# 08-MagnetSensor.net
KiCad netlist of a schematic drawn in Altium Designer
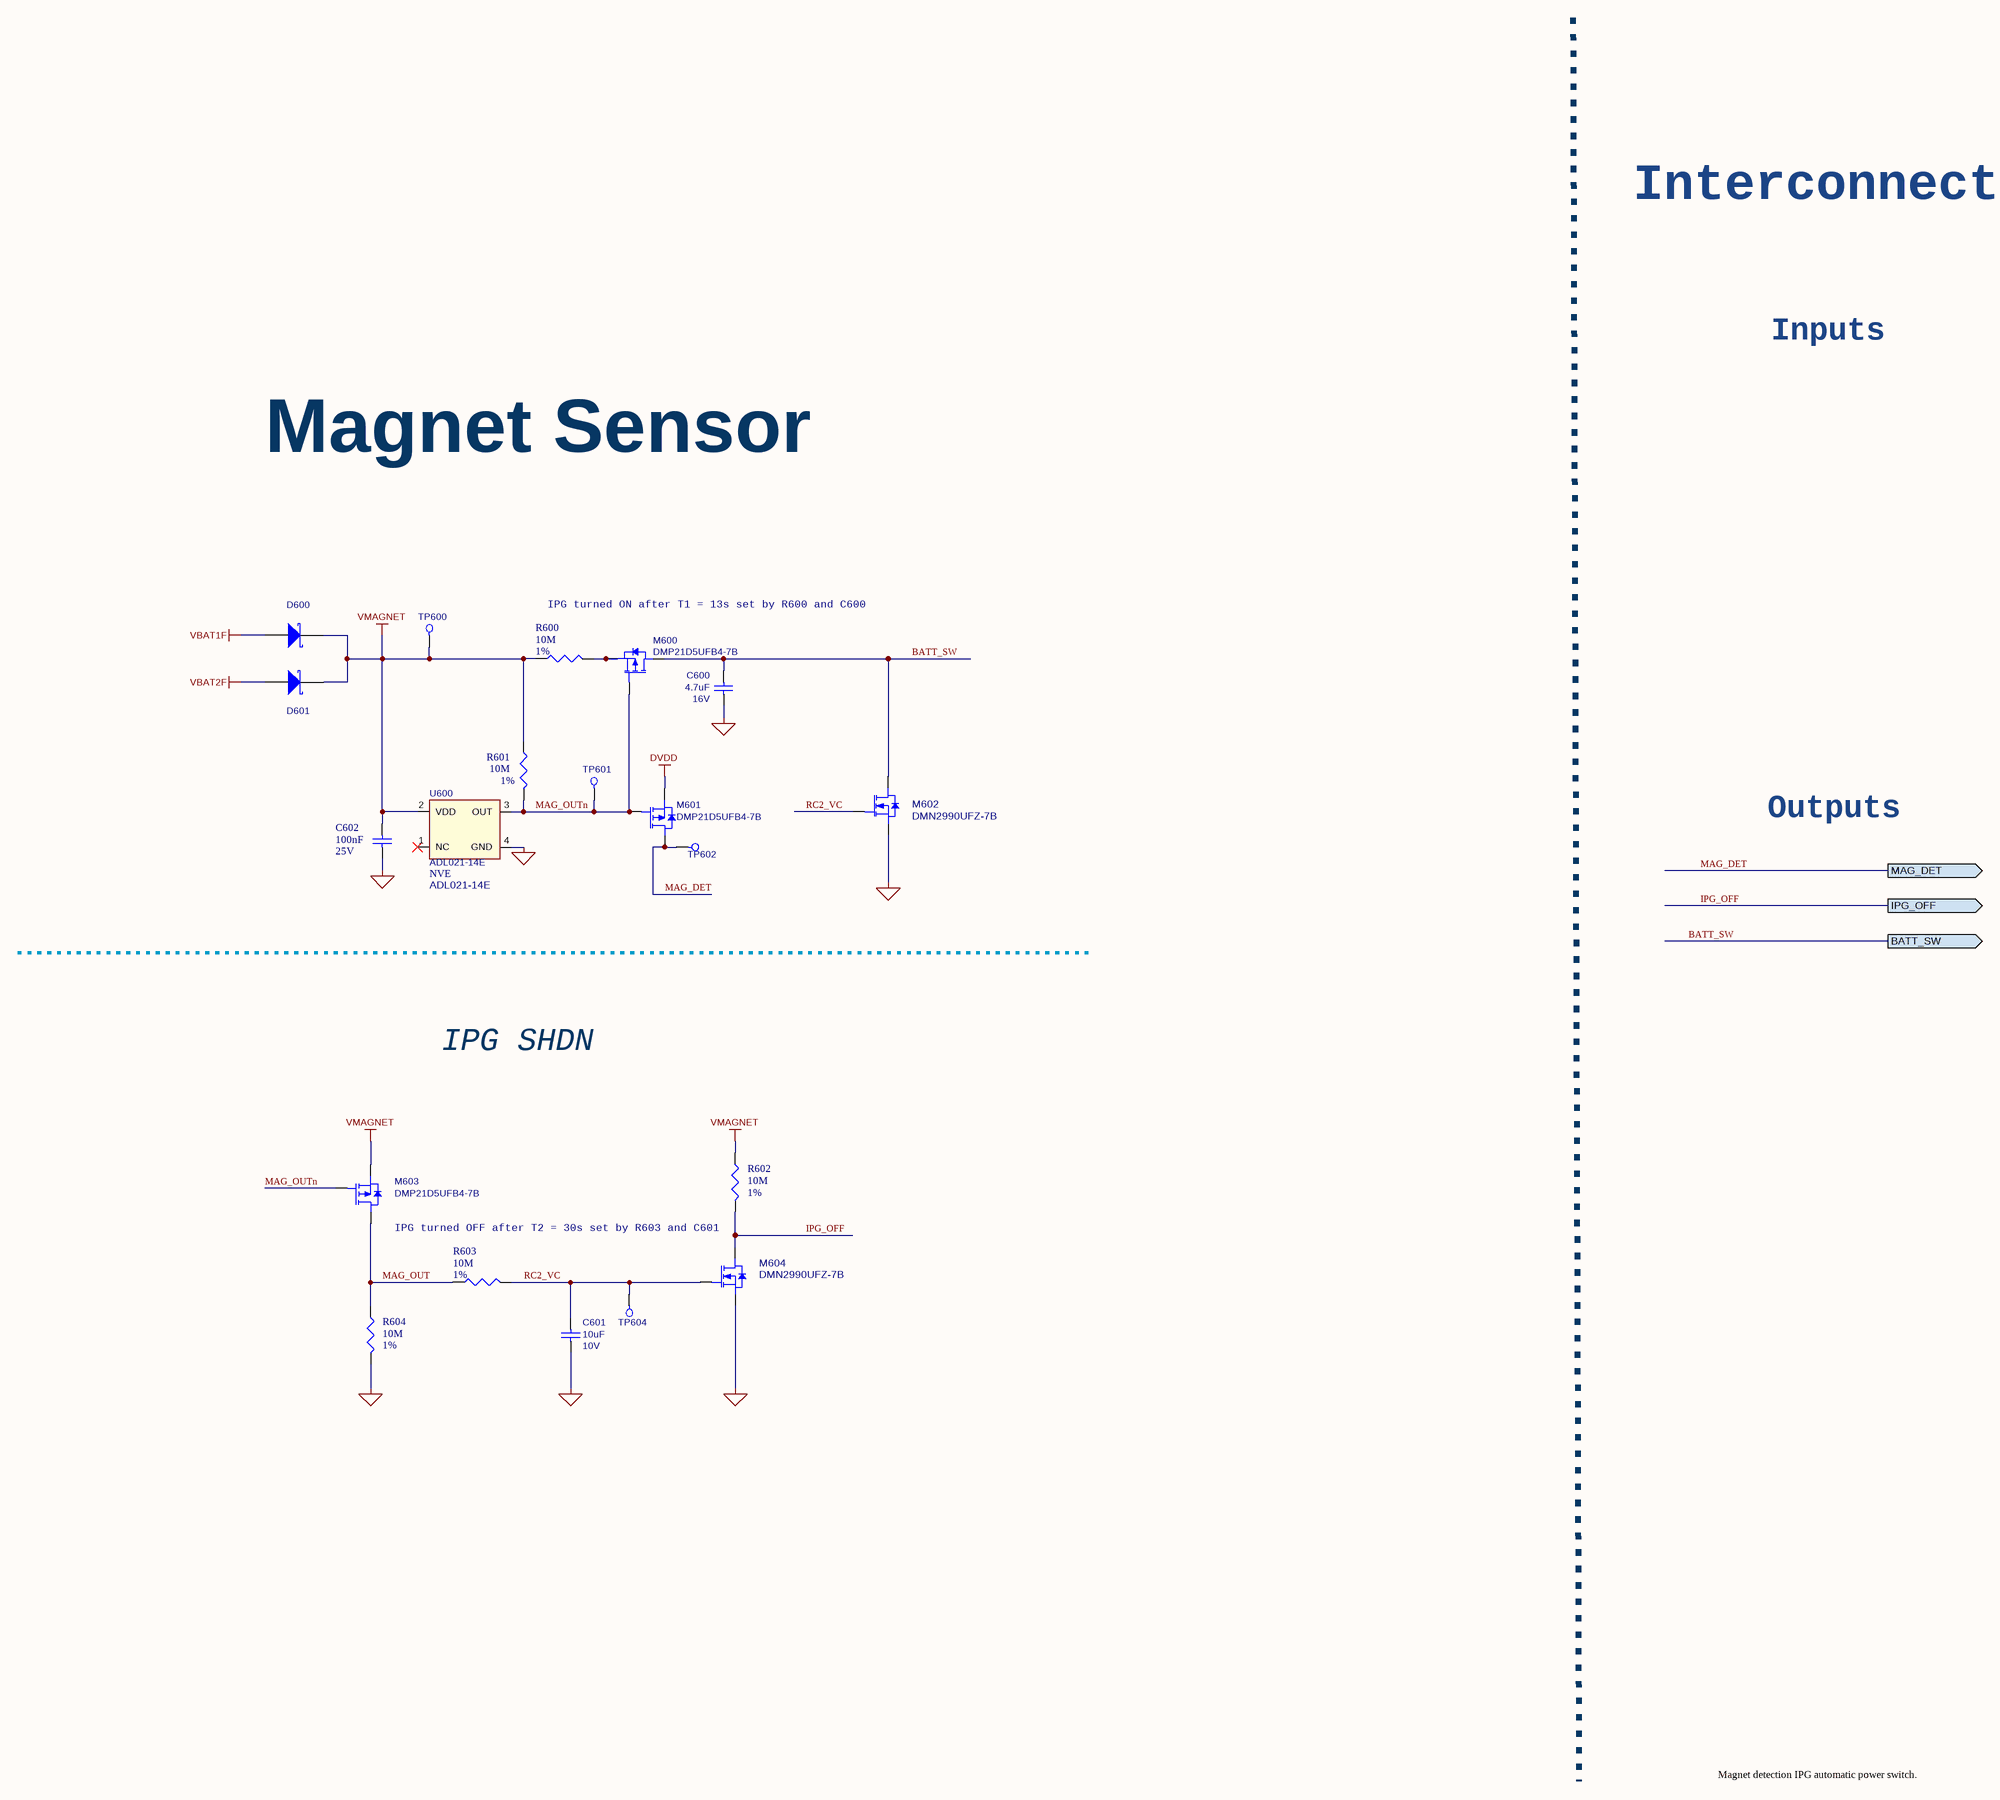
[diagram p0: 08-MagnetSensor.SchDoc]

(export (version "E")
  (design (tool "Eeschema 10.0.6"))
  (components
    (comp (ref "C600")
      (value "4.7uF")
      (footprint "CAP0603_REDUCED")
      (description "Capacitor, 4.7uF, X5R, 16V, 10%, 0603, Implant-grade")
      (fields
        (field (name "MANUFACTURER") "Murata")
        (field (name "RATING") "16V")
        (field (name "MANUFACTURER PART NUMBER") "GRM188R61C475KE11")
      )
      (libsource (lib "MP-LIBRARY") (part "GRM188R61C475KE11"))
    )
    (comp (ref "C601")
      (value "10uF")
      (footprint "CAP0402_REDUCED")
      (description "Capacitor, 10uf, X5R, 10V, 20%, 0402, Implant-grade")
      (fields
        (field (name "MANUFACTURER") "Murata")
        (field (name "RATING") "10V")
        (field (name "MANUFACTURER PART NUMBER") "ZRB15XR61A106ME01D")
      )
      (libsource (lib "MP-LIBRARY") (part "ZRB15XR61A106ME01D"))
    )
    (comp (ref "C602")
      (value "100nF")
      (footprint "C0201_C")
      (fields
        (field (name "MANUFACTURER") "Murata")
        (field (name "MANUFACTURER PART NUMBER") "GRM033R61E104KE14J")
        (field (name "RATED DC VOLTAGE (URDC)") "25V")
      )
      (libsource (lib "MP-LIBRARY") (part "GRM033R61E104KE14J"))
    )
    (comp (ref "D600")
      (value "NSR0130P2T5G")
      (footprint "ONSC_SOD-923_CASE514AB")
      (description "Schottky, 30V, 100mA, 385mV, 200mW, SOD-923")
      (fields (field (name "MANUFACTURER") "ON Semiconductor"))
      (libsource (lib "MP-LIBRARY") (part "NSR0130P2T5G"))
    )
    (comp (ref "D601")
      (value "NSR0130P2T5G")
      (footprint "ONSC_SOD-923_CASE514AB")
      (description "Schottky, 30V, 100mA, 385mV, 200mW, SOD-923")
      (fields (field (name "MANUFACTURER") "ON Semiconductor"))
      (libsource (lib "MP-LIBRARY") (part "NSR0130P2T5G"))
    )
    (comp (ref "M600")
      (value "DMP21D5UFB4-7B")
      (footprint "DIODESINC_X2-DFN1006-3_REDUCED")
      (description "MOSFET, P-chan, -20V, -400mA, X2-DFN1006-3")
      (fields (field (name "MANUFACTURER") "Diodes Inc"))
      (libsource (lib "MP-LIBRARY") (part "DMP21D5UFB4-7B"))
    )
    (comp (ref "M601")
      (value "DMP21D5UFB4-7B")
      (footprint "DIODESINC_X2-DFN1006-3_REDUCED")
      (description "MOSFET, P-chan, -20V, -400mA, X2-DFN1006-3")
      (fields (field (name "MANUFACTURER") "Diodes Inc"))
      (libsource (lib "MP-LIBRARY") (part "DMP21D5UFB4-7B"))
    )
    (comp (ref "M602")
      (value "DMN2990UFZ-7B")
      (footprint "DIODESINC_X2-DFN0606-3")
      (description "MOSFET, N-Chan, 20V, 170mA, DFN0606")
      (fields (field (name "MANUFACTURER") "Diodes Inc"))
      (libsource (lib "MP-LIBRARY") (part "DMN2990UFZ-7B"))
    )
    (comp (ref "M603")
      (value "DMP21D5UFB4-7B")
      (footprint "DIODESINC_X2-DFN1006-3_REDUCED")
      (description "MOSFET, P-chan, -20V, -400mA, X2-DFN1006-3")
      (fields (field (name "MANUFACTURER") "Diodes Inc"))
      (libsource (lib "MP-LIBRARY") (part "DMP21D5UFB4-7B"))
    )
    (comp (ref "M604")
      (value "DMN2990UFZ-7B")
      (footprint "DIODESINC_X2-DFN0606-3")
      (description "MOSFET, N-Chan, 20V, 170mA, DFN0606")
      (fields (field (name "MANUFACTURER") "Diodes Inc"))
      (libsource (lib "MP-LIBRARY") (part "DMN2990UFZ-7B"))
    )
    (comp (ref "R600")
      (value "10M")
      (footprint "R0201_C")
      (fields
        (field (name "MANUFACTURER") "Vishay Draloric")
        (field (name "MANUFACTURER PART NUMBER") "CRCW020110M0FNED")
        (field (name "TOLERANCE") "1%")
        (field (name "POWER") "50mW")
      )
      (libsource (lib "MP-LIBRARY") (part "CRCW020110M0FNED"))
    )
    (comp (ref "R601")
      (value "10M")
      (footprint "R0201_C")
      (fields
        (field (name "MANUFACTURER") "Vishay Draloric")
        (field (name "MANUFACTURER PART NUMBER") "CRCW020110M0FNED")
        (field (name "TOLERANCE") "1%")
        (field (name "POWER") "50mW")
      )
      (libsource (lib "MP-LIBRARY") (part "CRCW020110M0FNED"))
    )
    (comp (ref "R602")
      (value "10M")
      (footprint "R0201_C")
      (fields
        (field (name "MANUFACTURER") "Vishay Draloric")
        (field (name "MANUFACTURER PART NUMBER") "CRCW020110M0FNED")
        (field (name "TOLERANCE") "1%")
        (field (name "POWER") "50mW")
      )
      (libsource (lib "MP-LIBRARY") (part "CRCW020110M0FNED"))
    )
    (comp (ref "R603")
      (value "10M")
      (footprint "R0201_C")
      (fields
        (field (name "MANUFACTURER") "Vishay Draloric")
        (field (name "MANUFACTURER PART NUMBER") "CRCW020110M0FNED")
        (field (name "TOLERANCE") "1%")
        (field (name "POWER") "50mW")
      )
      (libsource (lib "MP-LIBRARY") (part "CRCW020110M0FNED"))
    )
    (comp (ref "R604")
      (value "10M")
      (footprint "R0201_C")
      (fields
        (field (name "MANUFACTURER") "Vishay Draloric")
        (field (name "MANUFACTURER PART NUMBER") "CRCW020110M0FNED")
        (field (name "TOLERANCE") "1%")
        (field (name "POWER") "50mW")
      )
      (libsource (lib "MP-LIBRARY") (part "CRCW020110M0FNED"))
    )
    (comp (ref "TP600")
      (value "Test Point")
      (footprint "testpad_0.9mm")
      (description "Test pad, 0.90mm circular pad")
      (libsource (lib "MP-LIBRARY") (part "Test Point"))
    )
    (comp (ref "TP601")
      (value "Test Point")
      (footprint "testpad_0.9mm")
      (description "Test pad, 0.90mm circular pad")
      (libsource (lib "MP-LIBRARY") (part "Test Point"))
    )
    (comp (ref "TP602")
      (value "Test Point")
      (footprint "testpad_0.9mm")
      (description "Test pad, 0.90mm circular pad")
      (libsource (lib "MP-LIBRARY") (part "Test Point"))
    )
    (comp (ref "TP604")
      (value "Test Point")
      (footprint "testpad_0.9mm")
      (description "Test pad, 0.90mm circular pad")
      (libsource (lib "MP-LIBRARY") (part "Test Point"))
    )
    (comp (ref "U600")
      (value "ADL021-14E")
      (footprint "NVE_ULLGA4")
      (description "Magnet Sensor, 15 Gauss, ULLGA4, Implant-grade")
      (fields (field (name "MANUFACTURER") "NVE") (field (name "ALTIUM_VALUE") "ADL021-14E"))
      (libsource (lib "MP-LIBRARY") (part "ADL021-14E"))
    )
  )
  (nets
    (net (code "1") (name "/BATT_SW") (class "Default")
      (node (ref "C600") (pin "1") (pinfunction "1_1") (pintype "passive"))
      (node (ref "M600") (pin "3") (pinfunction "D_3") (pintype "passive"))
      (node (ref "M602") (pin "3") (pinfunction "D_3") (pintype "passive"))
    )
    (net (code "2") (name "/IPG_OFF") (class "Default")
      (node (ref "M604") (pin "3") (pinfunction "D_3") (pintype "passive"))
      (node (ref "R602") (pin "2") (pinfunction "2_2") (pintype "passive"))
    )
    (net (code "3") (name "/MAG_DET") (class "Default")
      (node (ref "M601") (pin "3") (pinfunction "D_3") (pintype "passive"))
      (node (ref "TP602") (pin "1") (pinfunction "1_1") (pintype "passive"))
    )
    (net (code "4") (name "/MAG_OUT") (class "Default")
      (node (ref "M603") (pin "3") (pinfunction "D_3") (pintype "passive"))
      (node (ref "R603") (pin "1") (pinfunction "1_1") (pintype "passive"))
      (node (ref "R604") (pin "1") (pinfunction "1_1") (pintype "passive"))
    )
    (net (code "5") (name "/MAG_OUTn") (class "Default")
      (node (ref "M600") (pin "1") (pinfunction "G_1") (pintype "passive"))
      (node (ref "M601") (pin "1") (pinfunction "G_1") (pintype "passive"))
      (node (ref "M603") (pin "1") (pinfunction "G_1") (pintype "passive"))
      (node (ref "R601") (pin "2") (pinfunction "2_2") (pintype "passive"))
      (node (ref "TP601") (pin "1") (pinfunction "1_1") (pintype "passive"))
      (node (ref "U600") (pin "3") (pinfunction "OUT_3") (pintype "passive"))
    )
    (net (code "6") (name "/RC2_VC") (class "Default")
      (node (ref "C601") (pin "2") (pinfunction "2_2") (pintype "passive"))
      (node (ref "M602") (pin "1") (pinfunction "G_1") (pintype "passive"))
      (node (ref "M604") (pin "1") (pinfunction "G_1") (pintype "passive"))
      (node (ref "R603") (pin "2") (pinfunction "2_2") (pintype "passive"))
      (node (ref "TP604") (pin "1") (pinfunction "1_1") (pintype "passive"))
    )
    (net (code "7") (name "DVDD") (class "Default")
      (node (ref "M601") (pin "2") (pinfunction "S_2") (pintype "passive"))
    )
    (net (code "8") (name "GND") (class "Default")
      (node (ref "C600") (pin "2") (pinfunction "2_2") (pintype "passive"))
      (node (ref "C601") (pin "1") (pinfunction "1_1") (pintype "passive"))
      (node (ref "C602") (pin "1") (pinfunction "1_1") (pintype "passive"))
      (node (ref "M602") (pin "2") (pinfunction "S_2") (pintype "passive"))
      (node (ref "M604") (pin "2") (pinfunction "S_2") (pintype "passive"))
      (node (ref "R604") (pin "2") (pinfunction "2_2") (pintype "passive"))
      (node (ref "U600") (pin "4") (pinfunction "GND_4") (pintype "power_in"))
    )
    (net (code "9") (name "Net-(M600-S)") (class "Default")
      (node (ref "M600") (pin "2") (pinfunction "S_2") (pintype "passive"))
      (node (ref "R600") (pin "2") (pinfunction "2_2") (pintype "passive"))
    )
    (net (code "10") (name "VBAT1F") (class "Default")
      (node (ref "D600") (pin "2") (pinfunction "A_2") (pintype "passive"))
    )
    (net (code "11") (name "VBAT2F") (class "Default")
      (node (ref "D601") (pin "2") (pinfunction "A_2") (pintype "passive"))
    )
    (net (code "12") (name "VMAGNET") (class "Default")
      (node (ref "C602") (pin "2") (pinfunction "2_2") (pintype "passive"))
      (node (ref "D600") (pin "1") (pinfunction "K_1") (pintype "passive"))
      (node (ref "D601") (pin "1") (pinfunction "K_1") (pintype "passive"))
      (node (ref "M603") (pin "2") (pinfunction "S_2") (pintype "passive"))
      (node (ref "R600") (pin "1") (pinfunction "1_1") (pintype "passive"))
      (node (ref "R601") (pin "1") (pinfunction "1_1") (pintype "passive"))
      (node (ref "R602") (pin "1") (pinfunction "1_1") (pintype "passive"))
      (node (ref "TP600") (pin "1") (pinfunction "1_1") (pintype "passive"))
      (node (ref "U600") (pin "2") (pinfunction "VDD_2") (pintype "power_in"))
    )
    (net (code "13") (name "unconnected-(U600-NC-Pad1)") (class "Default")
      (node (ref "U600") (pin "1") (pinfunction "NC_1") (pintype "passive+no_connect"))
    )
  )
)
